# STRWL-S02-V00-12VProtection.net
KiCad netlist of a schematic drawn in Altium Designer
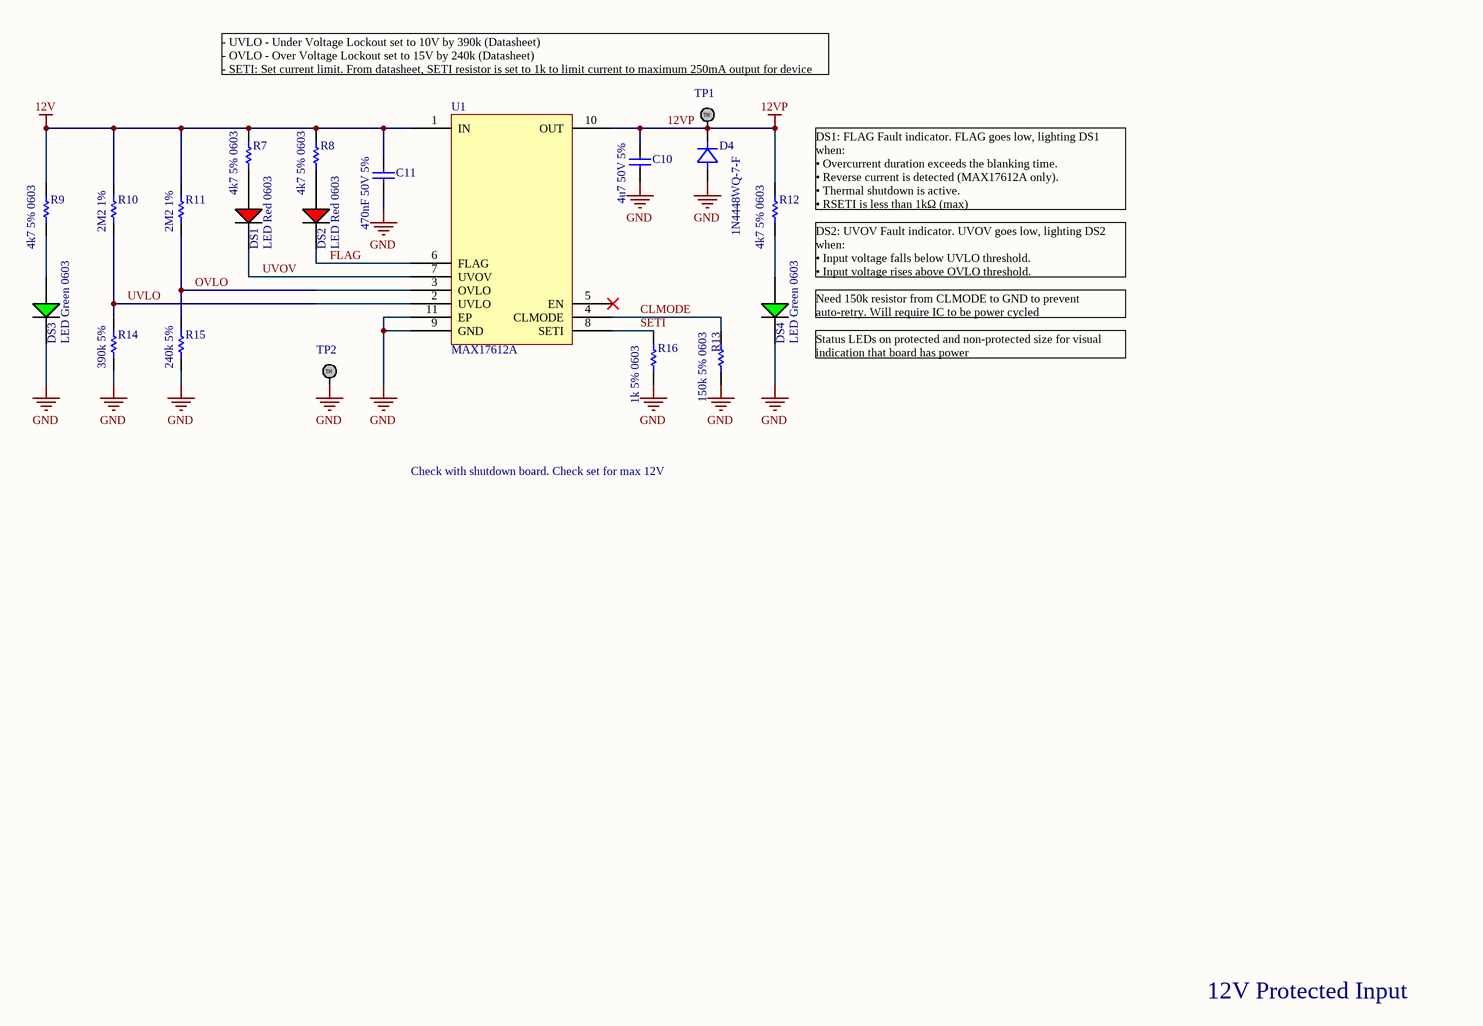
[diagram p0: STRWL-S02-V00-12VProtection.SchDoc]

(export (version "E")
  (design (tool "Eeschema 10.0.6"))
  (components
    (comp (ref "C10")
      (value "4u7 50V 5%")
      (footprint "Cap_Ceramic_0603")
      (description "Capacitor, Ceramic, SMD, 4u7, 50V, 5%, X7R, 0603")
      (libsource (lib "StandardCapacitors") (part "4u7 50V 5% X7R 0603"))
    )
    (comp (ref "C11")
      (value "470nF 50V 5%")
      (footprint "Cap_Ceramic_0603")
      (description "Capacitor, Ceramic, SMD, 470nF, 50V, 5%, X7R, 0603")
      (libsource (lib "StandardCapacitors") (part "470nF 50V 5% X7R 0603"))
    )
    (comp (ref "D4")
      (value "1N4448WQ-7-F")
      (footprint "SMA")
      (description "Diode, SMD, 75V, 5%, 250mA, SOD123")
      (fields
        (field (name "MANUFACTURER") "ON Semiconductor / Fairchild")
        (field (name "MANUFACTURER PART NUMBER") "1N914BWS")
      )
      (libsource (lib "QUTMS_DiodeLibrary") (part "1N4448WQ-7-F"))
    )
    (comp (ref "DS1")
      (value "LED Red 0603")
      (footprint "LED RED 0603")
      (libsource (lib "QUTMS_LEDLibrary") (part "LED Red 0603"))
    )
    (comp (ref "DS2")
      (value "LED Red 0603")
      (footprint "LED RED 0603")
      (libsource (lib "QUTMS_LEDLibrary") (part "LED Red 0603"))
    )
    (comp (ref "DS3")
      (value "LED Green 0603")
      (footprint "LED GREEN 0603")
      (libsource (lib "QUTMS_LEDLibrary") (part "LED Green 0603"))
    )
    (comp (ref "DS4")
      (value "LED Green 0603")
      (footprint "LED GREEN 0603")
      (libsource (lib "QUTMS_LEDLibrary") (part "LED Green 0603"))
    )
    (comp (ref "R7")
      (value "4k7 5% 0603")
      (footprint "Res_ThinFilm_0603")
      (description "Resistor, SMD, 4k7, 0.1W, 5%, 0603")
      (libsource (lib "StandardResistors") (part "4k7 5% 0603"))
    )
    (comp (ref "R8")
      (value "4k7 5% 0603")
      (footprint "Res_ThinFilm_0603")
      (description "Resistor, SMD, 4k7, 0.1W, 5%, 0603")
      (libsource (lib "StandardResistors") (part "4k7 5% 0603"))
    )
    (comp (ref "R9")
      (value "4k7 5% 0603")
      (footprint "Res_ThinFilm_0603")
      (description "Resistor, SMD, 4k7, 0.1W, 5%, 0603")
      (libsource (lib "StandardResistors") (part "4k7 5% 0603"))
    )
    (comp (ref "R10")
      (value "2M2 1%")
      (footprint "Res_ThinFilm_0603")
      (description "Resistor, SMD, 2M2, 0.125W, 1%, 0603")
      (libsource (lib "StandardResistors") (part "2M2 1% 0603"))
    )
    (comp (ref "R11")
      (value "2M2 1%")
      (footprint "Res_ThinFilm_0603")
      (description "Resistor, SMD, 2M2, 0.125W, 1%, 0603")
      (libsource (lib "StandardResistors") (part "2M2 1% 0603"))
    )
    (comp (ref "R12")
      (value "4k7 5% 0603")
      (footprint "Res_ThinFilm_0603")
      (description "Resistor, SMD, 4k7, 0.1W, 5%, 0603")
      (libsource (lib "StandardResistors") (part "4k7 5% 0603"))
    )
    (comp (ref "R13")
      (value "150k 5% 0603")
      (footprint "Res_ThinFilm_0603")
      (description "Resistor, SMD, 150k, 0.1W, 5%, 0603")
      (libsource (lib "StandardResistors") (part "150k 5%, 0603"))
    )
    (comp (ref "R14")
      (value "390k 5%")
      (footprint "Res_ThinFilm_0603")
      (description "Resistor, SMD, 390k, 0.1W, 5%, 0603")
      (libsource (lib "StandardResistors") (part "390k 5% 0603"))
    )
    (comp (ref "R15")
      (value "240k 5%")
      (footprint "Res_ThinFilm_0603")
      (description "Resistor, SMD, 240k, 0.1W, 5%, 0603")
      (libsource (lib "StandardResistors") (part "240k 5% 0603"))
    )
    (comp (ref "R16")
      (value "1k 5% 0603")
      (footprint "Res_ThinFilm_0603")
      (description "Resistor, SMD, 1k, 0.1W, 5%, 0603")
      (libsource (lib "StandardResistors") (part "1k 5% 0603"))
    )
    (comp (ref "TP1")
      (value "TestPoint")
      (footprint "TestPointSMD")
      (libsource (lib "StandardTest") (part "TestPoint"))
    )
    (comp (ref "TP2")
      (value "TestPoint")
      (footprint "TestPointSMD")
      (libsource (lib "StandardTest") (part "TestPoint"))
    )
    (comp (ref "U1")
      (value "MAX17612A")
      (footprint "MAX17612A")
      (description "4.5V to 60V, 250mA Current-Limiter with OV, UV, and Reverse Protection")
      (libsource (lib "QUTMS-MCISOLibrary") (part "MAX17612A"))
    )
  )
  (nets
    (net (code "1") (name "/CLMODE") (class "Default")
      (node (ref "R13") (pin "2") (pinfunction "2_2") (pintype "passive"))
      (node (ref "U1") (pin "4") (pinfunction "CLMODE_4") (pintype "passive"))
    )
    (net (code "2") (name "/FLAG") (class "Default")
      (node (ref "DS2") (pin "2") (pinfunction "C_2") (pintype "passive"))
      (node (ref "U1") (pin "6") (pinfunction "FLAG_6") (pintype "passive"))
    )
    (net (code "3") (name "/OVLO") (class "Default")
      (node (ref "R11") (pin "1") (pinfunction "1_1") (pintype "passive"))
      (node (ref "R15") (pin "2") (pinfunction "2_2") (pintype "passive"))
      (node (ref "U1") (pin "3") (pinfunction "OVLO_3") (pintype "passive"))
    )
    (net (code "4") (name "/SETI") (class "Default")
      (node (ref "R16") (pin "2") (pinfunction "2_2") (pintype "passive"))
      (node (ref "U1") (pin "8") (pinfunction "SETI_8") (pintype "passive"))
    )
    (net (code "5") (name "/UVLO") (class "Default")
      (node (ref "R10") (pin "1") (pinfunction "1_1") (pintype "passive"))
      (node (ref "R14") (pin "2") (pinfunction "2_2") (pintype "passive"))
      (node (ref "U1") (pin "2") (pinfunction "UVLO_2") (pintype "passive"))
    )
    (net (code "6") (name "/UVOV") (class "Default")
      (node (ref "DS1") (pin "2") (pinfunction "C_2") (pintype "passive"))
      (node (ref "U1") (pin "7") (pinfunction "UVOV_7") (pintype "passive"))
    )
    (net (code "7") (name "12V") (class "Default")
      (node (ref "C11") (pin "2") (pinfunction "2_2") (pintype "passive"))
      (node (ref "R10") (pin "2") (pinfunction "2_2") (pintype "passive"))
      (node (ref "R11") (pin "2") (pinfunction "2_2") (pintype "passive"))
      (node (ref "R7") (pin "2") (pinfunction "2_2") (pintype "passive"))
      (node (ref "R8") (pin "2") (pinfunction "2_2") (pintype "passive"))
      (node (ref "R9") (pin "2") (pinfunction "2_2") (pintype "passive"))
      (node (ref "U1") (pin "1") (pinfunction "IN_1") (pintype "passive"))
    )
    (net (code "8") (name "12VP") (class "Default")
      (node (ref "C10") (pin "2") (pinfunction "2_2") (pintype "passive"))
      (node (ref "D4") (pin "K") (pinfunction "Cathode_K") (pintype "passive"))
      (node (ref "R12") (pin "2") (pinfunction "2_2") (pintype "passive"))
      (node (ref "TP1") (pin "1") (pinfunction "1_1") (pintype "passive"))
      (node (ref "U1") (pin "10") (pinfunction "OUT_10") (pintype "passive"))
    )
    (net (code "9") (name "GND") (class "Default")
      (node (ref "C10") (pin "1") (pinfunction "1_1") (pintype "passive"))
      (node (ref "C11") (pin "1") (pinfunction "1_1") (pintype "passive"))
      (node (ref "D4") (pin "A") (pinfunction "Anode_A") (pintype "passive"))
      (node (ref "DS3") (pin "2") (pinfunction "C_2") (pintype "passive"))
      (node (ref "DS4") (pin "2") (pinfunction "C_2") (pintype "passive"))
      (node (ref "R13") (pin "1") (pinfunction "1_1") (pintype "passive"))
      (node (ref "R14") (pin "1") (pinfunction "1_1") (pintype "passive"))
      (node (ref "R15") (pin "1") (pinfunction "1_1") (pintype "passive"))
      (node (ref "R16") (pin "1") (pinfunction "1_1") (pintype "passive"))
      (node (ref "TP2") (pin "1") (pinfunction "1_1") (pintype "passive"))
      (node (ref "U1") (pin "11") (pinfunction "EP_11") (pintype "passive"))
      (node (ref "U1") (pin "9") (pinfunction "GND_9") (pintype "passive"))
    )
    (net (code "10") (name "Net-(DS1-A)") (class "Default")
      (node (ref "DS1") (pin "1") (pinfunction "A_1") (pintype "passive"))
      (node (ref "R7") (pin "1") (pinfunction "1_1") (pintype "passive"))
    )
    (net (code "11") (name "Net-(DS2-A)") (class "Default")
      (node (ref "DS2") (pin "1") (pinfunction "A_1") (pintype "passive"))
      (node (ref "R8") (pin "1") (pinfunction "1_1") (pintype "passive"))
    )
    (net (code "12") (name "Net-(DS3-A)") (class "Default")
      (node (ref "DS3") (pin "1") (pinfunction "A_1") (pintype "passive"))
      (node (ref "R9") (pin "1") (pinfunction "1_1") (pintype "passive"))
    )
    (net (code "13") (name "Net-(DS4-A)") (class "Default")
      (node (ref "DS4") (pin "1") (pinfunction "A_1") (pintype "passive"))
      (node (ref "R12") (pin "1") (pinfunction "1_1") (pintype "passive"))
    )
    (net (code "14") (name "unconnected-(U1-EN-Pad5)") (class "Default")
      (node (ref "U1") (pin "5") (pinfunction "EN_5") (pintype "passive+no_connect"))
    )
  )
)
